# relayBoard.net
KiCad netlist of a schematic drawn in EAGLE
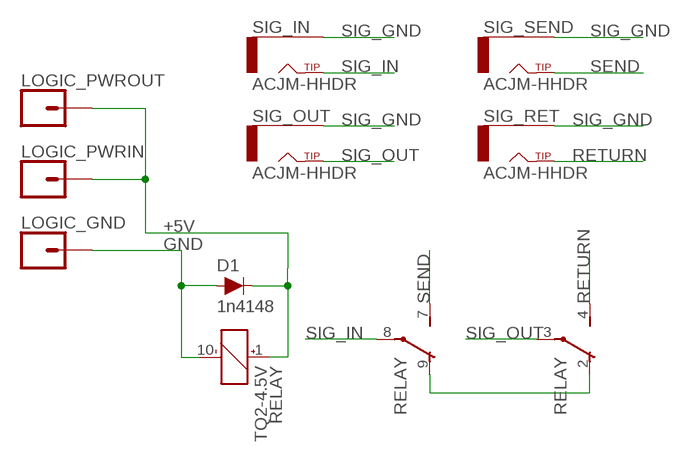
[diagram p0: schematic, sheet 1]

(export (version "E")
  (design (tool "Eeschema 10.0.6"))
  (components
    (comp (ref "D1")
      (value "1n4148")
      (footprint "eagle-import:DIODE-1N4148")
      (libsource (lib "eagle-import") (part "DIODE-1N4148"))
    )
    (comp (ref "LOGIC_GND")
      (value "CONN_01")
      (footprint "eagle-import:1X01")
      (libsource (lib "eagle-import") (part "CONN_01"))
    )
    (comp (ref "LOGIC_PWRIN")
      (value "CONN_01")
      (footprint "eagle-import:1X01")
      (libsource (lib "eagle-import") (part "CONN_01"))
    )
    (comp (ref "LOGIC_PWROUT")
      (value "CONN_01")
      (footprint "eagle-import:1X01")
      (libsource (lib "eagle-import") (part "CONN_01"))
    )
    (comp (ref "RELAY")
      (value "TQ2-4.5V")
      (footprint "eagle-import:TQ2")
      (fields (field (name "MF") "AROMAT/ MATSUSHITA"))
      (libsource (lib "eagle-import") (part "TQ2?-4.5V"))
    )
    (comp (ref "SIG_IN")
      (value "ACJM-HHDR")
      (footprint "eagle-import:ACJM-HHDR")
      (libsource (lib "eagle-import") (part "ACJM-HHDR"))
    )
    (comp (ref "SIG_OUT")
      (value "ACJM-HHDR")
      (footprint "eagle-import:ACJM-HHDR")
      (libsource (lib "eagle-import") (part "ACJM-HHDR"))
    )
    (comp (ref "SIG_RET")
      (value "ACJM-HHDR")
      (footprint "eagle-import:ACJM-HHDR")
      (libsource (lib "eagle-import") (part "ACJM-HHDR"))
    )
    (comp (ref "SIG_SEND")
      (value "ACJM-HHDR")
      (footprint "eagle-import:ACJM-HHDR")
      (libsource (lib "eagle-import") (part "ACJM-HHDR"))
    )
  )
  (nets
    (net (code "1") (name "/+5V") (class "Default")
      (node (ref "D1") (pin "C") (pinfunction "C_C") (pintype "passive"))
      (node (ref "LOGIC_PWRIN") (pin "1") (pinfunction "1_1") (pintype "passive"))
      (node (ref "LOGIC_PWROUT") (pin "1") (pinfunction "1_1") (pintype "passive"))
      (node (ref "RELAY") (pin "1") (pinfunction "+_1") (pintype "passive"))
    )
    (net (code "2") (name "/GND") (class "Default")
      (node (ref "D1") (pin "A") (pinfunction "A_A") (pintype "passive"))
      (node (ref "LOGIC_GND") (pin "1") (pinfunction "1_1") (pintype "passive"))
      (node (ref "RELAY") (pin "10") (pinfunction "-_10") (pintype "passive"))
    )
    (net (code "3") (name "/RETURN") (class "Default")
      (node (ref "RELAY") (pin "4") (pinfunction "S_4") (pintype "passive"))
      (node (ref "SIG_RET") (pin "TIP_1") (pinfunction "TIP_TIP_1") (pintype "bidirectional"))
      (node (ref "SIG_RET") (pin "TIP_2") (pinfunction "TIP_TIP_2") (pintype "bidirectional"))
    )
    (net (code "4") (name "/SEND") (class "Default")
      (node (ref "RELAY") (pin "7") (pinfunction "S_7") (pintype "passive"))
      (node (ref "SIG_SEND") (pin "TIP_1") (pinfunction "TIP_TIP_1") (pintype "bidirectional"))
      (node (ref "SIG_SEND") (pin "TIP_2") (pinfunction "TIP_TIP_2") (pintype "bidirectional"))
    )
    (net (code "5") (name "/SIG_GND") (class "Default")
      (node (ref "SIG_IN") (pin "SLEEVE_1") (pinfunction "SLEEVE_SLEEVE_1") (pintype "bidirectional"))
      (node (ref "SIG_IN") (pin "SLEEVE_2") (pinfunction "SLEEVE_SLEEVE_2") (pintype "bidirectional"))
      (node (ref "SIG_OUT") (pin "SLEEVE_1") (pinfunction "SLEEVE_SLEEVE_1") (pintype "bidirectional"))
      (node (ref "SIG_OUT") (pin "SLEEVE_2") (pinfunction "SLEEVE_SLEEVE_2") (pintype "bidirectional"))
      (node (ref "SIG_RET") (pin "SLEEVE_1") (pinfunction "SLEEVE_SLEEVE_1") (pintype "bidirectional"))
      (node (ref "SIG_RET") (pin "SLEEVE_2") (pinfunction "SLEEVE_SLEEVE_2") (pintype "bidirectional"))
      (node (ref "SIG_SEND") (pin "SLEEVE_1") (pinfunction "SLEEVE_SLEEVE_1") (pintype "bidirectional"))
      (node (ref "SIG_SEND") (pin "SLEEVE_2") (pinfunction "SLEEVE_SLEEVE_2") (pintype "bidirectional"))
    )
    (net (code "6") (name "/SIG_IN") (class "Default")
      (node (ref "RELAY") (pin "8") (pinfunction "P_8") (pintype "passive"))
      (node (ref "SIG_IN") (pin "TIP_1") (pinfunction "TIP_TIP_1") (pintype "bidirectional"))
      (node (ref "SIG_IN") (pin "TIP_2") (pinfunction "TIP_TIP_2") (pintype "bidirectional"))
    )
    (net (code "7") (name "/SIG_OUT") (class "Default")
      (node (ref "RELAY") (pin "3") (pinfunction "P_3") (pintype "passive"))
      (node (ref "SIG_OUT") (pin "TIP_1") (pinfunction "TIP_TIP_1") (pintype "bidirectional"))
      (node (ref "SIG_OUT") (pin "TIP_2") (pinfunction "TIP_TIP_2") (pintype "bidirectional"))
    )
    (net (code "8") (name "Net-(RELAYA-O)") (class "Default")
      (node (ref "RELAY") (pin "2") (pinfunction "O_2") (pintype "passive"))
      (node (ref "RELAY") (pin "9") (pinfunction "O_9") (pintype "passive"))
    )
  )
)
